# Power_Opamp.net
KiCad netlist of a schematic drawn in EAGLE
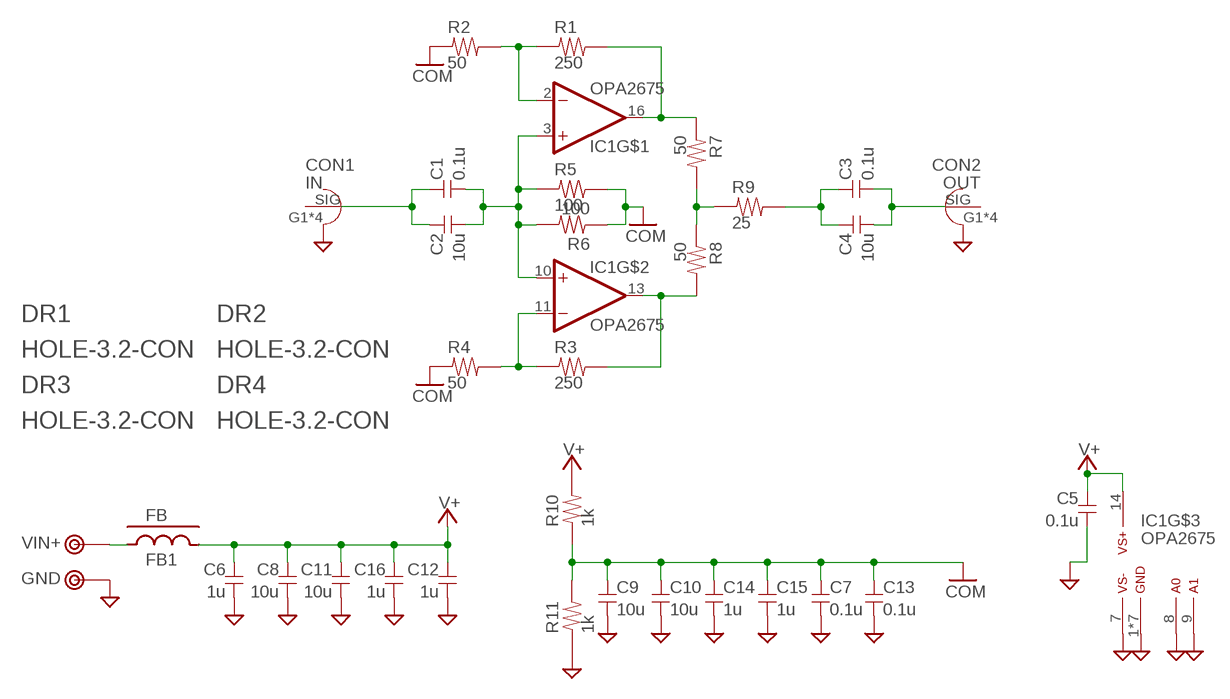
[diagram p0: schematic, sheet 1]

(export (version "E")
  (design (tool "Eeschema 10.0.6"))
  (components
    (comp (ref "C1")
      (value "0.1u")
      (footprint "eagle-import:1608C")
      (libsource (lib "eagle-import") (part "C-1608"))
    )
    (comp (ref "C2")
      (value "10u")
      (footprint "eagle-import:2012")
      (libsource (lib "eagle-import") (part "C-2012"))
    )
    (comp (ref "C3")
      (value "0.1u")
      (footprint "eagle-import:1608C")
      (libsource (lib "eagle-import") (part "C-1608"))
    )
    (comp (ref "C4")
      (value "10u")
      (footprint "eagle-import:2012")
      (libsource (lib "eagle-import") (part "C-2012"))
    )
    (comp (ref "C5")
      (value "0.1u")
      (footprint "eagle-import:1005")
      (libsource (lib "eagle-import") (part "C-1005"))
    )
    (comp (ref "C6")
      (value "1u")
      (footprint "eagle-import:1608C")
      (libsource (lib "eagle-import") (part "C-1608"))
    )
    (comp (ref "C7")
      (value "0.1u")
      (footprint "eagle-import:1005")
      (libsource (lib "eagle-import") (part "C-1005"))
    )
    (comp (ref "C8")
      (value "10u")
      (footprint "eagle-import:3216")
      (libsource (lib "eagle-import") (part "C-3216"))
    )
    (comp (ref "C9")
      (value "10u")
      (footprint "eagle-import:3216")
      (libsource (lib "eagle-import") (part "C-3216"))
    )
    (comp (ref "C10")
      (value "10u")
      (footprint "eagle-import:2012")
      (libsource (lib "eagle-import") (part "C-2012"))
    )
    (comp (ref "C11")
      (value "10u")
      (footprint "eagle-import:2012")
      (libsource (lib "eagle-import") (part "C-2012"))
    )
    (comp (ref "C12")
      (value "1u")
      (footprint "eagle-import:1608C")
      (libsource (lib "eagle-import") (part "C-1608"))
    )
    (comp (ref "C13")
      (value "0.1u")
      (footprint "eagle-import:1005")
      (libsource (lib "eagle-import") (part "C-1005"))
    )
    (comp (ref "C14")
      (value "1u")
      (footprint "eagle-import:1608C")
      (libsource (lib "eagle-import") (part "C-1608"))
    )
    (comp (ref "C15")
      (value "1u")
      (footprint "eagle-import:1608C")
      (libsource (lib "eagle-import") (part "C-1608"))
    )
    (comp (ref "C16")
      (value "1u")
      (footprint "eagle-import:1608C")
      (libsource (lib "eagle-import") (part "C-1608"))
    )
    (comp (ref "CON1")
      (value "IN")
      (footprint "eagle-import:SMA-EDGE")
      (libsource (lib "eagle-import") (part "SMA-142-0701-801"))
    )
    (comp (ref "CON2")
      (value "OUT")
      (footprint "eagle-import:SMA-EDGE")
      (libsource (lib "eagle-import") (part "SMA-142-0701-801"))
    )
    (comp (ref "DR1")
      (value "HOLE-3.2-CON")
      (footprint "eagle-import:HOLE_3.2_CON")
      (libsource (lib "eagle-import") (part "HOLE-3.2-CON"))
    )
    (comp (ref "DR2")
      (value "HOLE-3.2-CON")
      (footprint "eagle-import:HOLE_3.2_CON")
      (libsource (lib "eagle-import") (part "HOLE-3.2-CON"))
    )
    (comp (ref "DR3")
      (value "HOLE-3.2-CON")
      (footprint "eagle-import:HOLE_3.2_CON")
      (libsource (lib "eagle-import") (part "HOLE-3.2-CON"))
    )
    (comp (ref "DR4")
      (value "HOLE-3.2-CON")
      (footprint "eagle-import:HOLE_3.2_CON")
      (libsource (lib "eagle-import") (part "HOLE-3.2-CON"))
    )
    (comp (ref "FB1")
      (value "FB")
      (footprint "eagle-import:2012-J")
      (libsource (lib "eagle-import") (part "FB-2012"))
    )
    (comp (ref "IC1")
      (value "OPA2675")
      (footprint "eagle-import:VQFN16")
      (libsource (lib "eagle-import") (part "OPA2675"))
    )
    (comp (ref "R1")
      (value "250")
      (footprint "eagle-import:1608-3")
      (libsource (lib "eagle-import") (part "R-1608-3"))
    )
    (comp (ref "R2")
      (value "50")
      (footprint "eagle-import:1608-3")
      (libsource (lib "eagle-import") (part "R-1608-3"))
    )
    (comp (ref "R3")
      (value "250")
      (footprint "eagle-import:1608-3")
      (libsource (lib "eagle-import") (part "R-1608-3"))
    )
    (comp (ref "R4")
      (value "50")
      (footprint "eagle-import:1608-3")
      (libsource (lib "eagle-import") (part "R-1608-3"))
    )
    (comp (ref "R5")
      (value "100")
      (footprint "eagle-import:1608-3")
      (libsource (lib "eagle-import") (part "R-1608-3"))
    )
    (comp (ref "R6")
      (value "100")
      (footprint "eagle-import:1608-3")
      (libsource (lib "eagle-import") (part "R-1608-3"))
    )
    (comp (ref "R7")
      (value "50")
      (footprint "eagle-import:1608")
      (libsource (lib "eagle-import") (part "R-1608"))
    )
    (comp (ref "R8")
      (value "50")
      (footprint "eagle-import:1608")
      (libsource (lib "eagle-import") (part "R-1608"))
    )
    (comp (ref "R9")
      (value "25")
      (footprint "eagle-import:1608")
      (libsource (lib "eagle-import") (part "R-1608"))
    )
    (comp (ref "R10")
      (value "1k")
      (footprint "eagle-import:1608")
      (libsource (lib "eagle-import") (part "R-1608"))
    )
    (comp (ref "R11")
      (value "1k")
      (footprint "eagle-import:1608")
      (libsource (lib "eagle-import") (part "R-1608"))
    )
    (comp (ref "TP1")
      (value "VIN+")
      (footprint "eagle-import:TESTPIN-BIG")
      (libsource (lib "eagle-import") (part "TESTPIN-BIG"))
    )
    (comp (ref "TP2")
      (value "GND")
      (footprint "eagle-import:TESTPIN-BIG")
      (libsource (lib "eagle-import") (part "TESTPIN-BIG"))
    )
  )
  (nets
    (net (code "1") (name "COM") (class "Default")
      (node (ref "C10") (pin "1") (pinfunction "1_1") (pintype "passive"))
      (node (ref "C13") (pin "1") (pinfunction "1_1") (pintype "passive"))
      (node (ref "C14") (pin "1") (pinfunction "1_1") (pintype "passive"))
      (node (ref "C15") (pin "1") (pinfunction "1_1") (pintype "passive"))
      (node (ref "C7") (pin "1") (pinfunction "1_1") (pintype "passive"))
      (node (ref "C9") (pin "1") (pinfunction "1_1") (pintype "passive"))
      (node (ref "R10") (pin "1") (pinfunction "1_1") (pintype "passive"))
      (node (ref "R11") (pin "2") (pinfunction "2_2") (pintype "passive"))
      (node (ref "R2") (pin "1") (pinfunction "1_1") (pintype "passive"))
      (node (ref "R4") (pin "1") (pinfunction "1_1") (pintype "passive"))
      (node (ref "R5") (pin "2") (pinfunction "2_2") (pintype "passive"))
      (node (ref "R6") (pin "1") (pinfunction "1_1") (pintype "passive"))
    )
    (net (code "2") (name "GND") (class "Default")
      (node (ref "C10") (pin "2") (pinfunction "2_2") (pintype "passive"))
      (node (ref "C11") (pin "2") (pinfunction "2_2") (pintype "passive"))
      (node (ref "C12") (pin "2") (pinfunction "2_2") (pintype "passive"))
      (node (ref "C13") (pin "2") (pinfunction "2_2") (pintype "passive"))
      (node (ref "C14") (pin "2") (pinfunction "2_2") (pintype "passive"))
      (node (ref "C15") (pin "2") (pinfunction "2_2") (pintype "passive"))
      (node (ref "C16") (pin "2") (pinfunction "2_2") (pintype "passive"))
      (node (ref "C5") (pin "2") (pinfunction "2_2") (pintype "passive"))
      (node (ref "C6") (pin "2") (pinfunction "2_2") (pintype "passive"))
      (node (ref "C7") (pin "2") (pinfunction "2_2") (pintype "passive"))
      (node (ref "C8") (pin "2") (pinfunction "2_2") (pintype "passive"))
      (node (ref "C9") (pin "2") (pinfunction "2_2") (pintype "passive"))
      (node (ref "CON1") (pin "G1") (pinfunction "GND_G1") (pintype "passive"))
      (node (ref "CON1") (pin "G2") (pinfunction "GND_G2") (pintype "passive"))
      (node (ref "CON1") (pin "G3") (pinfunction "GND_G3") (pintype "passive"))
      (node (ref "CON1") (pin "G4") (pinfunction "GND_G4") (pintype "passive"))
      (node (ref "CON2") (pin "G1") (pinfunction "GND_G1") (pintype "passive"))
      (node (ref "CON2") (pin "G2") (pinfunction "GND_G2") (pintype "passive"))
      (node (ref "CON2") (pin "G3") (pinfunction "GND_G3") (pintype "passive"))
      (node (ref "CON2") (pin "G4") (pinfunction "GND_G4") (pintype "passive"))
      (node (ref "IC1") (pin "1") (pinfunction "GND_1") (pintype "input"))
      (node (ref "IC1") (pin "12") (pinfunction "GND_12") (pintype "input"))
      (node (ref "IC1") (pin "15") (pinfunction "GND_15") (pintype "input"))
      (node (ref "IC1") (pin "4") (pinfunction "GND_4") (pintype "input"))
      (node (ref "IC1") (pin "5") (pinfunction "GND_5") (pintype "input"))
      (node (ref "IC1") (pin "6") (pinfunction "GND_6") (pintype "input"))
      (node (ref "IC1") (pin "7") (pinfunction "VS-_7") (pintype "input"))
      (node (ref "IC1") (pin "8") (pinfunction "A0_8") (pintype "input"))
      (node (ref "IC1") (pin "9") (pinfunction "A1_9") (pintype "input"))
      (node (ref "IC1") (pin "HT") (pinfunction "GND_HT") (pintype "input"))
      (node (ref "R11") (pin "1") (pinfunction "1_1") (pintype "passive"))
      (node (ref "TP2") (pin "1") (pinfunction "1_1") (pintype "passive"))
    )
    (net (code "3") (name "Net-(C1-Pad1)") (class "Default")
      (node (ref "C1") (pin "1") (pinfunction "1_1") (pintype "passive"))
      (node (ref "C2") (pin "1") (pinfunction "1_1") (pintype "passive"))
      (node (ref "CON1") (pin "SIG") (pinfunction "SIG_SIG") (pintype "passive"))
    )
    (net (code "4") (name "Net-(C3-Pad1)") (class "Default")
      (node (ref "C3") (pin "1") (pinfunction "1_1") (pintype "passive"))
      (node (ref "C4") (pin "1") (pinfunction "1_1") (pintype "passive"))
      (node (ref "R9") (pin "2") (pinfunction "2_2") (pintype "passive"))
    )
    (net (code "5") (name "Net-(C3-Pad2)") (class "Default")
      (node (ref "C3") (pin "2") (pinfunction "2_2") (pintype "passive"))
      (node (ref "C4") (pin "2") (pinfunction "2_2") (pintype "passive"))
      (node (ref "CON2") (pin "SIG") (pinfunction "SIG_SIG") (pintype "passive"))
    )
    (net (code "6") (name "Net-(FB1-Pad2)") (class "Default")
      (node (ref "FB1") (pin "2") (pinfunction "2_2") (pintype "passive"))
      (node (ref "TP1") (pin "1") (pinfunction "1_1") (pintype "passive"))
    )
    (net (code "7") (name "Net-(IC1A-+IN)") (class "Default")
      (node (ref "C1") (pin "2") (pinfunction "2_2") (pintype "passive"))
      (node (ref "C2") (pin "2") (pinfunction "2_2") (pintype "passive"))
      (node (ref "IC1") (pin "10") (pinfunction "+IN_10") (pintype "input"))
      (node (ref "IC1") (pin "3") (pinfunction "+IN_3") (pintype "input"))
      (node (ref "R5") (pin "1") (pinfunction "1_1") (pintype "passive"))
      (node (ref "R6") (pin "2") (pinfunction "2_2") (pintype "passive"))
    )
    (net (code "8") (name "Net-(IC1A--IN)") (class "Default")
      (node (ref "IC1") (pin "2") (pinfunction "-IN_2") (pintype "input"))
      (node (ref "R1") (pin "1") (pinfunction "1_1") (pintype "passive"))
      (node (ref "R2") (pin "2") (pinfunction "2_2") (pintype "passive"))
    )
    (net (code "9") (name "Net-(IC1A-OUT)") (class "Default")
      (node (ref "IC1") (pin "16") (pinfunction "OUT_16") (pintype "output"))
      (node (ref "R1") (pin "2") (pinfunction "2_2") (pintype "passive"))
      (node (ref "R7") (pin "1") (pinfunction "1_1") (pintype "passive"))
    )
    (net (code "10") (name "Net-(IC1B--IN)") (class "Default")
      (node (ref "IC1") (pin "11") (pinfunction "-IN_11") (pintype "input"))
      (node (ref "R3") (pin "1") (pinfunction "1_1") (pintype "passive"))
      (node (ref "R4") (pin "2") (pinfunction "2_2") (pintype "passive"))
    )
    (net (code "11") (name "Net-(IC1B-OUT)") (class "Default")
      (node (ref "IC1") (pin "13") (pinfunction "OUT_13") (pintype "output"))
      (node (ref "R3") (pin "2") (pinfunction "2_2") (pintype "passive"))
      (node (ref "R8") (pin "2") (pinfunction "2_2") (pintype "passive"))
    )
    (net (code "12") (name "Net-(R7-Pad2)") (class "Default")
      (node (ref "R7") (pin "2") (pinfunction "2_2") (pintype "passive"))
      (node (ref "R8") (pin "1") (pinfunction "1_1") (pintype "passive"))
      (node (ref "R9") (pin "1") (pinfunction "1_1") (pintype "passive"))
    )
    (net (code "13") (name "V+") (class "Default")
      (node (ref "C11") (pin "1") (pinfunction "1_1") (pintype "passive"))
      (node (ref "C12") (pin "1") (pinfunction "1_1") (pintype "passive"))
      (node (ref "C16") (pin "1") (pinfunction "1_1") (pintype "passive"))
      (node (ref "C5") (pin "1") (pinfunction "1_1") (pintype "passive"))
      (node (ref "C6") (pin "1") (pinfunction "1_1") (pintype "passive"))
      (node (ref "C8") (pin "1") (pinfunction "1_1") (pintype "passive"))
      (node (ref "FB1") (pin "1") (pinfunction "1_1") (pintype "passive"))
      (node (ref "IC1") (pin "14") (pinfunction "VS+_14") (pintype "input"))
      (node (ref "R10") (pin "2") (pinfunction "2_2") (pintype "passive"))
    )
  )
)
